# PID.net
KiCad netlist of a schematic drawn in Altium Designer
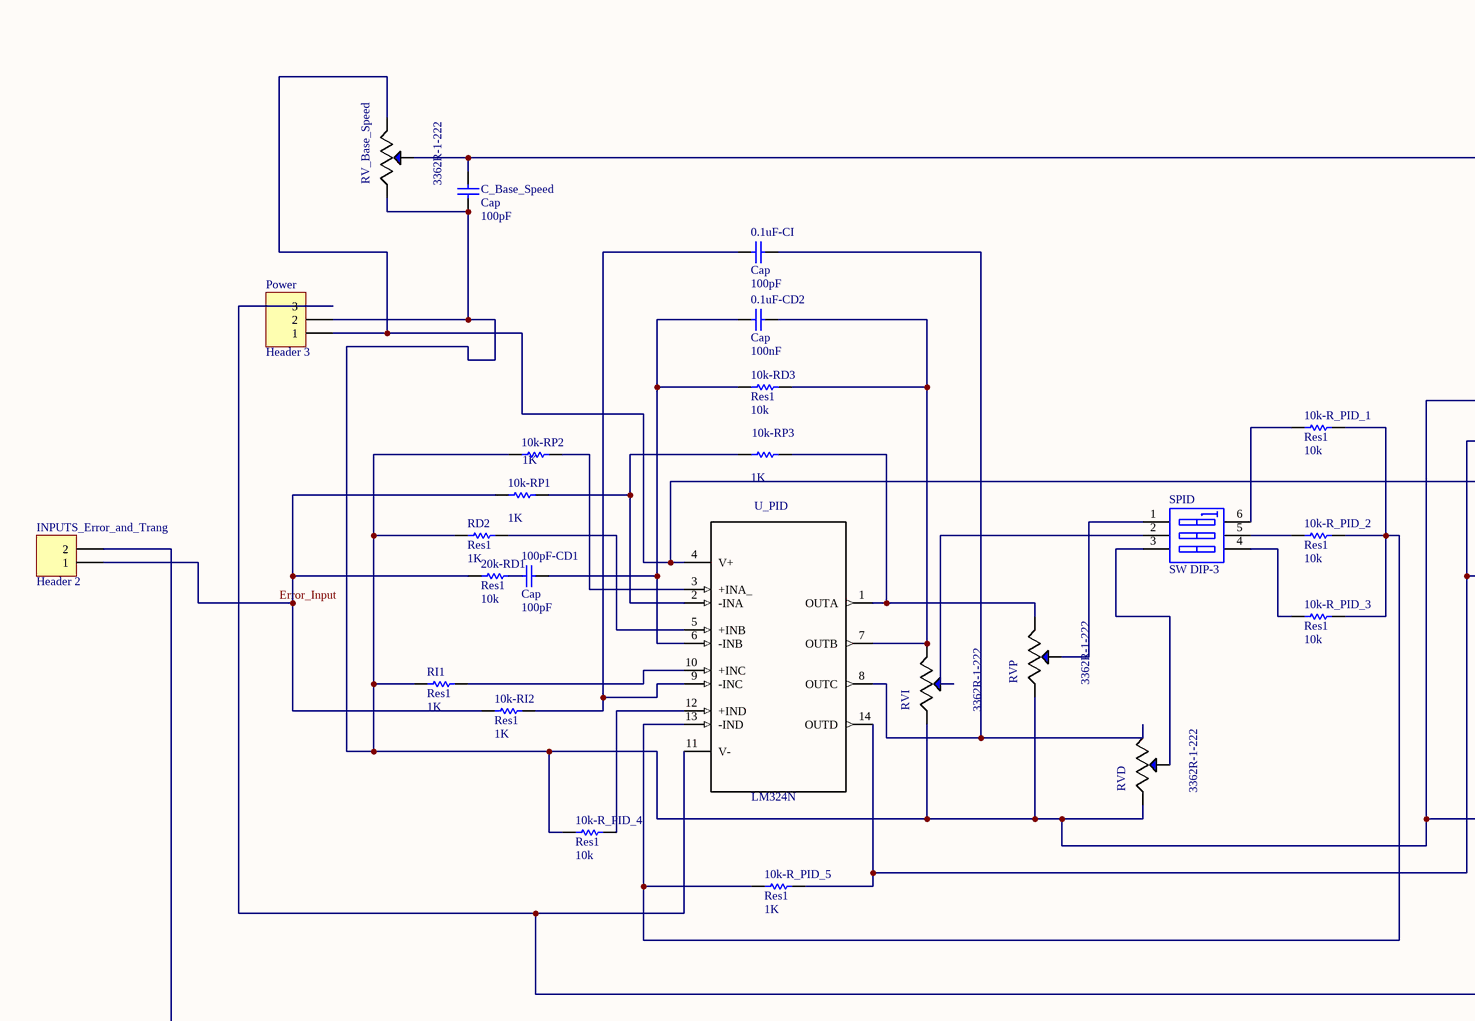
[diagram p0: PID.SchDoc, left]
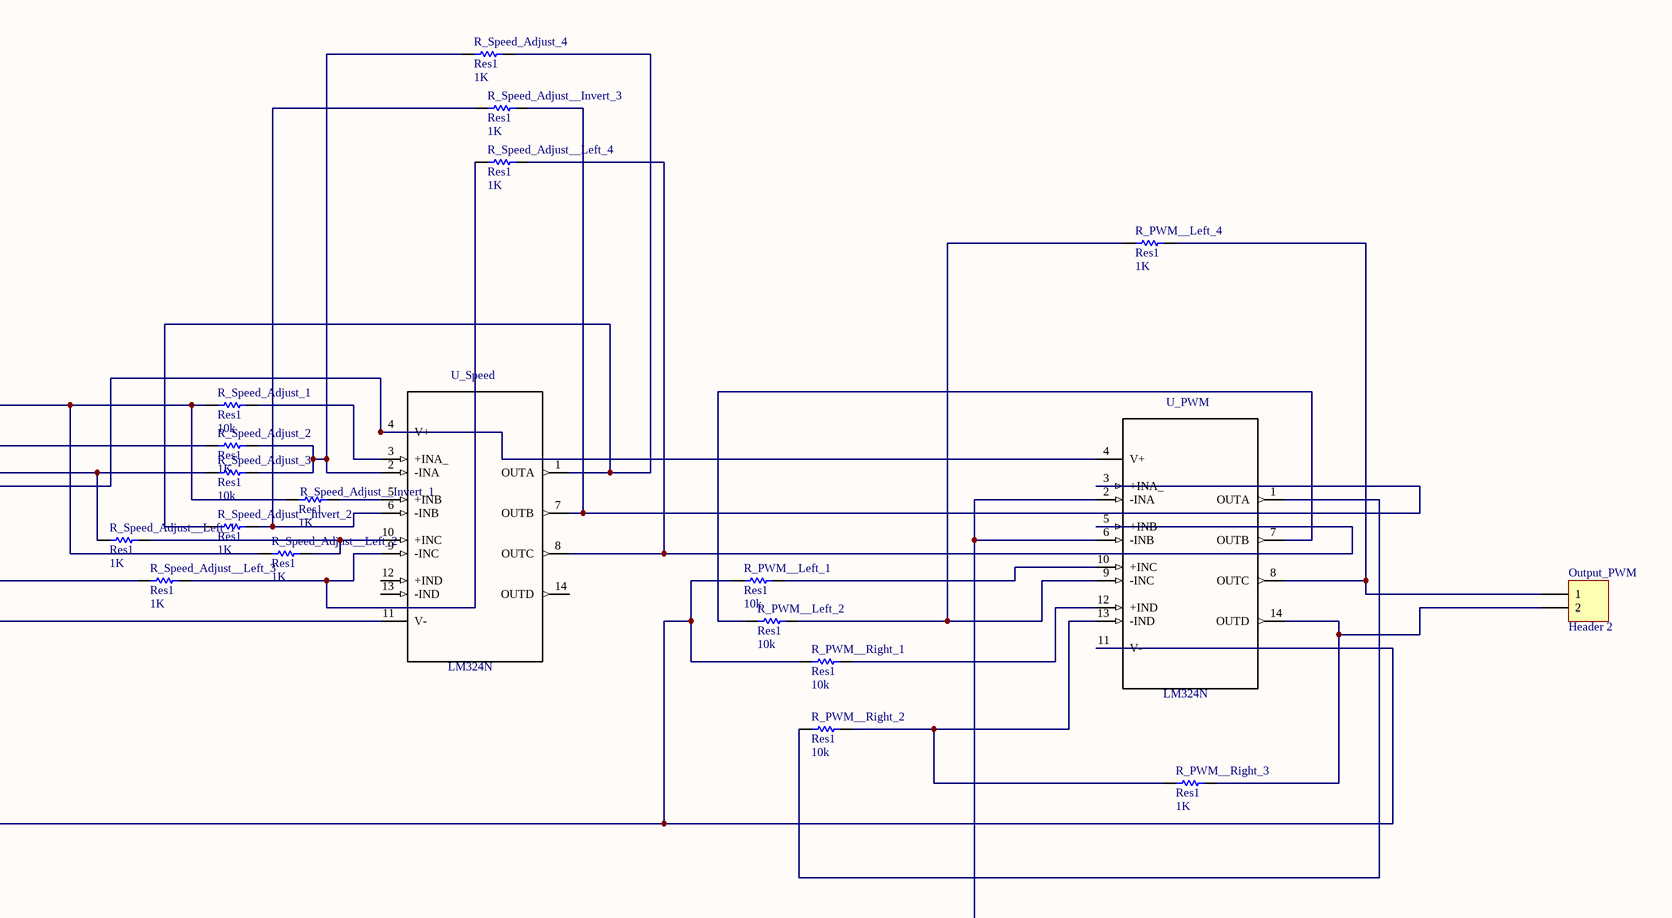
[diagram p1: PID.SchDoc, right]

(export (version "E")
  (design (tool "Eeschema 10.0.6"))
  (components
    (comp (ref "0.1uF-CD2")
      (value "Cap")
      (footprint "RAD-0.3")
      (description "Capacitor")
      (fields (field (name "ALTIUM_VALUE") "100nF") (field (name "PUBLISHER") "Altium Limited"))
      (libsource (lib "Miscellaneous Devices") (part "Cap"))
    )
    (comp (ref "0.1uF-CI")
      (value "Cap")
      (footprint "RAD-0.3")
      (description "Capacitor")
      (fields (field (name "ALTIUM_VALUE") "100pF") (field (name "PUBLISHER") "Altium Limited"))
      (libsource (lib "Miscellaneous Devices") (part "Cap"))
    )
    (comp (ref "10k-RD3")
      (value "Res1")
      (footprint "AXIAL-0.3")
      (description "Resistor")
      (fields (field (name "ALTIUM_VALUE") "10k") (field (name "PUBLISHER") "Altium Limited"))
      (libsource (lib "Miscellaneous Devices") (part "Res1"))
    )
    (comp (ref "10k-RI2")
      (value "Res1")
      (footprint "AXIAL-0.3")
      (description "Resistor")
      (fields (field (name "ALTIUM_VALUE") "1K") (field (name "PUBLISHER") "Altium Limited"))
      (libsource (lib "Miscellaneous Devices") (part "Res1"))
    )
    (comp (ref "10k-RP1")
      (value "1K")
      (footprint "AXIAL-0.3")
      (description "Resistor")
      (fields (field (name "PUBLISHER") "Altium Limited"))
      (libsource (lib "Miscellaneous Devices") (part "Res1"))
    )
    (comp (ref "10k-RP2")
      (value "1K")
      (footprint "AXIAL-0.3")
      (description "Resistor")
      (fields (field (name "PUBLISHER") "Altium Limited"))
      (libsource (lib "Miscellaneous Devices") (part "Res1"))
    )
    (comp (ref "10k-RP3")
      (value "1K")
      (footprint "AXIAL-0.3")
      (description "Resistor")
      (fields (field (name "PUBLISHER") "Altium Limited"))
      (libsource (lib "Miscellaneous Devices") (part "Res1"))
    )
    (comp (ref "10k-R_PID_1")
      (value "Res1")
      (footprint "AXIAL-0.3")
      (description "Resistor")
      (fields (field (name "ALTIUM_VALUE") "10k") (field (name "PUBLISHER") "Altium Limited"))
      (libsource (lib "Miscellaneous Devices") (part "Res1"))
    )
    (comp (ref "10k-R_PID_2")
      (value "Res1")
      (footprint "AXIAL-0.3")
      (description "Resistor")
      (fields (field (name "ALTIUM_VALUE") "10k") (field (name "PUBLISHER") "Altium Limited"))
      (libsource (lib "Miscellaneous Devices") (part "Res1"))
    )
    (comp (ref "10k-R_PID_3")
      (value "Res1")
      (footprint "AXIAL-0.3")
      (description "Resistor")
      (fields (field (name "ALTIUM_VALUE") "10k") (field (name "PUBLISHER") "Altium Limited"))
      (libsource (lib "Miscellaneous Devices") (part "Res1"))
    )
    (comp (ref "10k-R_PID_4")
      (value "Res1")
      (footprint "AXIAL-0.3")
      (description "Resistor")
      (fields (field (name "ALTIUM_VALUE") "10k") (field (name "PUBLISHER") "Altium Limited"))
      (libsource (lib "Miscellaneous Devices") (part "Res1"))
    )
    (comp (ref "10k-R_PID_5")
      (value "Res1")
      (footprint "AXIAL-0.3")
      (description "Resistor")
      (fields (field (name "ALTIUM_VALUE") "1K") (field (name "PUBLISHER") "Altium Limited"))
      (libsource (lib "Miscellaneous Devices") (part "Res1"))
    )
    (comp (ref "20k-RD1")
      (value "Res1")
      (footprint "AXIAL-0.3")
      (description "Resistor")
      (fields (field (name "ALTIUM_VALUE") "10k") (field (name "PUBLISHER") "Altium Limited"))
      (libsource (lib "Miscellaneous Devices") (part "Res1"))
    )
    (comp (ref "100pF-CD1")
      (value "Cap")
      (footprint "RAD-0.3")
      (description "Capacitor")
      (fields (field (name "ALTIUM_VALUE") "100pF") (field (name "PUBLISHER") "Altium Limited"))
      (libsource (lib "Miscellaneous Devices") (part "Cap"))
    )
    (comp (ref "C_Base_Speed")
      (value "Cap")
      (footprint "RAD-0.3")
      (description "Capacitor")
      (fields (field (name "ALTIUM_VALUE") "100pF") (field (name "PUBLISHER") "Altium Limited"))
      (libsource (lib "Miscellaneous Devices") (part "Cap"))
    )
    (comp (ref "INPUTS_Error_and_Trang")
      (value "Header 2")
      (footprint "HDR1X2")
      (description "Header, 2-Pin")
      (fields (field (name "PUBLISHER") "Altium Limited"))
      (libsource (lib "") (part "Header 2_1"))
    )
    (comp (ref "Output_PWM")
      (value "Header 2")
      (footprint "HDR1X2")
      (description "Header, 2-Pin")
      (fields (field (name "PUBLISHER") "Altium Limited"))
      (libsource (lib "Miscellaneous Connectors") (part "Header 2"))
    )
    (comp (ref "Power")
      (value "Header 3")
      (footprint "HDR1X3")
      (description "Header, 3-Pin")
      (fields (field (name "PUBLISHER") "Altium Limited"))
      (libsource (lib "Miscellaneous Connectors") (part "Header 3"))
    )
    (comp (ref "RD2")
      (value "Res1")
      (footprint "AXIAL-0.3")
      (description "Resistor")
      (fields (field (name "ALTIUM_VALUE") "1K") (field (name "PUBLISHER") "Altium Limited"))
      (libsource (lib "Miscellaneous Devices") (part "Res1"))
    )
    (comp (ref "RI1")
      (value "Res1")
      (footprint "AXIAL-0.3")
      (description "Resistor")
      (fields (field (name "ALTIUM_VALUE") "1K") (field (name "PUBLISHER") "Altium Limited"))
      (libsource (lib "Miscellaneous Devices") (part "Res1"))
    )
    (comp (ref "RVD")
      (value "3362R-1-222")
      (footprint "*TRIM_3362R-1-222")
      (description "Trimpot 2.2k Ohm 1/4 Sq Cer St")
      (fields (field (name "MF") "Bourns"))
      (libsource (lib "3362R-1-222") (part "3362R-1-222"))
    )
    (comp (ref "RVI")
      (value "3362R-1-222")
      (footprint "*TRIM_3362R-1-222")
      (description "Trimpot 2.2k Ohm 1/4 Sq Cer St")
      (fields (field (name "MF") "Bourns"))
      (libsource (lib "3362R-1-222") (part "3362R-1-222"))
    )
    (comp (ref "RVP")
      (value "3362R-1-222")
      (footprint "*TRIM_3362R-1-222")
      (description "Trimpot 2.2k Ohm 1/4 Sq Cer St")
      (fields (field (name "MF") "Bourns"))
      (libsource (lib "3362R-1-222") (part "3362R-1-222"))
    )
    (comp (ref "RV_Base_Speed")
      (value "3362R-1-222")
      (footprint "*TRIM_3362R-1-222")
      (description "Trimpot 2.2k Ohm 1/4 Sq Cer St")
      (fields (field (name "MF") "Bourns"))
      (libsource (lib "3362R-1-222") (part "3362R-1-222"))
    )
    (comp (ref "R_PWM__Left_1")
      (value "Res1")
      (footprint "AXIAL-0.3")
      (description "Resistor")
      (fields (field (name "ALTIUM_VALUE") "10k") (field (name "PUBLISHER") "Altium Limited"))
      (libsource (lib "Miscellaneous Devices") (part "Res1"))
    )
    (comp (ref "R_PWM__Left_2")
      (value "Res1")
      (footprint "AXIAL-0.3")
      (description "Resistor")
      (fields (field (name "ALTIUM_VALUE") "10k") (field (name "PUBLISHER") "Altium Limited"))
      (libsource (lib "Miscellaneous Devices") (part "Res1"))
    )
    (comp (ref "R_PWM__Left_4")
      (value "Res1")
      (footprint "AXIAL-0.3")
      (description "Resistor")
      (fields (field (name "ALTIUM_VALUE") "1K") (field (name "PUBLISHER") "Altium Limited"))
      (libsource (lib "Miscellaneous Devices") (part "Res1"))
    )
    (comp (ref "R_PWM__Right_1")
      (value "Res1")
      (footprint "AXIAL-0.3")
      (description "Resistor")
      (fields (field (name "ALTIUM_VALUE") "10k") (field (name "PUBLISHER") "Altium Limited"))
      (libsource (lib "Miscellaneous Devices") (part "Res1"))
    )
    (comp (ref "R_PWM__Right_2")
      (value "Res1")
      (footprint "AXIAL-0.3")
      (description "Resistor")
      (fields (field (name "ALTIUM_VALUE") "10k") (field (name "PUBLISHER") "Altium Limited"))
      (libsource (lib "Miscellaneous Devices") (part "Res1"))
    )
    (comp (ref "R_PWM__Right_3")
      (value "Res1")
      (footprint "AXIAL-0.3")
      (description "Resistor")
      (fields (field (name "ALTIUM_VALUE") "1K") (field (name "PUBLISHER") "Altium Limited"))
      (libsource (lib "Miscellaneous Devices") (part "Res1"))
    )
    (comp (ref "R_Speed_Adjust_1")
      (value "Res1")
      (footprint "AXIAL-0.3")
      (description "Resistor")
      (fields (field (name "ALTIUM_VALUE") "10k") (field (name "PUBLISHER") "Altium Limited"))
      (libsource (lib "Miscellaneous Devices") (part "Res1"))
    )
    (comp (ref "R_Speed_Adjust_2")
      (value "Res1")
      (footprint "AXIAL-0.3")
      (description "Resistor")
      (fields (field (name "ALTIUM_VALUE") "1K") (field (name "PUBLISHER") "Altium Limited"))
      (libsource (lib "Miscellaneous Devices") (part "Res1"))
    )
    (comp (ref "R_Speed_Adjust_3")
      (value "Res1")
      (footprint "AXIAL-0.3")
      (description "Resistor")
      (fields (field (name "ALTIUM_VALUE") "10k") (field (name "PUBLISHER") "Altium Limited"))
      (libsource (lib "Miscellaneous Devices") (part "Res1"))
    )
    (comp (ref "R_Speed_Adjust_4")
      (value "Res1")
      (footprint "AXIAL-0.3")
      (description "Resistor")
      (fields (field (name "ALTIUM_VALUE") "1K") (field (name "PUBLISHER") "Altium Limited"))
      (libsource (lib "Miscellaneous Devices") (part "Res1"))
    )
    (comp (ref "R_Speed_Adjust__Invert_1")
      (value "Res1")
      (footprint "AXIAL-0.3")
      (description "Resistor")
      (fields (field (name "ALTIUM_VALUE") "1K") (field (name "PUBLISHER") "Altium Limited"))
      (libsource (lib "Miscellaneous Devices") (part "Res1"))
    )
    (comp (ref "R_Speed_Adjust__Invert_2")
      (value "Res1")
      (footprint "AXIAL-0.3")
      (description "Resistor")
      (fields (field (name "ALTIUM_VALUE") "1K") (field (name "PUBLISHER") "Altium Limited"))
      (libsource (lib "Miscellaneous Devices") (part "Res1"))
    )
    (comp (ref "R_Speed_Adjust__Invert_3")
      (value "Res1")
      (footprint "AXIAL-0.3")
      (description "Resistor")
      (fields (field (name "ALTIUM_VALUE") "1K") (field (name "PUBLISHER") "Altium Limited"))
      (libsource (lib "Miscellaneous Devices") (part "Res1"))
    )
    (comp (ref "R_Speed_Adjust__Left_1")
      (value "Res1")
      (footprint "AXIAL-0.3")
      (description "Resistor")
      (fields (field (name "ALTIUM_VALUE") "1K") (field (name "PUBLISHER") "Altium Limited"))
      (libsource (lib "Miscellaneous Devices") (part "Res1"))
    )
    (comp (ref "R_Speed_Adjust__Left_2")
      (value "Res1")
      (footprint "AXIAL-0.3")
      (description "Resistor")
      (fields (field (name "ALTIUM_VALUE") "1K") (field (name "PUBLISHER") "Altium Limited"))
      (libsource (lib "Miscellaneous Devices") (part "Res1"))
    )
    (comp (ref "R_Speed_Adjust__Left_3")
      (value "Res1")
      (footprint "AXIAL-0.3")
      (description "Resistor")
      (fields (field (name "ALTIUM_VALUE") "1K") (field (name "PUBLISHER") "Altium Limited"))
      (libsource (lib "Miscellaneous Devices") (part "Res1"))
    )
    (comp (ref "R_Speed_Adjust__Left_4")
      (value "Res1")
      (footprint "AXIAL-0.3")
      (description "Resistor")
      (fields (field (name "ALTIUM_VALUE") "1K") (field (name "PUBLISHER") "Altium Limited"))
      (libsource (lib "Miscellaneous Devices") (part "Res1"))
    )
    (comp (ref "SPID")
      (value "SW DIP-3")
      (footprint "DIP-6")
      (description "DIP Switch, 3 Position, SPST")
      (fields (field (name "PUBLISHER") "Altium Limited"))
      (libsource (lib "Miscellaneous Devices") (part "SW DIP-3"))
    )
    (comp (ref "U_PID")
      (value "LM324N")
      (footprint "*DIP254P762X508-14")
      (description "OP Amp Quad GP ?15V/30V 14-Pin PDIP Tube")
      (fields (field (name "MF") "ON Semiconductor"))
      (libsource (lib "LM324N") (part "LM324N"))
    )
    (comp (ref "U_PWM")
      (value "LM324N")
      (footprint "*DIP254P762X508-14")
      (description "OP Amp Quad GP ?15V/30V 14-Pin PDIP Tube")
      (fields (field (name "MF") "ON Semiconductor"))
      (libsource (lib "LM324N") (part "LM324N"))
    )
    (comp (ref "U_Speed")
      (value "LM324N")
      (footprint "*DIP254P762X508-14")
      (description "OP Amp Quad GP ?15V/30V 14-Pin PDIP Tube")
      (fields (field (name "MF") "ON Semiconductor"))
      (libsource (lib "LM324N") (part "LM324N"))
    )
  )
  (nets
    (net (code "1") (name "/Error_Input") (class "Default")
      (node (ref "10k-RI2") (pin "1") (pinfunction "1_1") (pintype "passive"))
      (node (ref "10k-RP1") (pin "1") (pinfunction "1_1") (pintype "passive"))
      (node (ref "20k-RD1") (pin "1") (pinfunction "1_1") (pintype "passive"))
      (node (ref "INPUTS_Error_and_Trang") (pin "1") (pinfunction "1_1") (pintype "passive"))
    )
    (net (code "2") (name "Net-(100pF-CD1-Pad1)") (class "Default")
      (node (ref "100pF-CD1") (pin "1") (pinfunction "1_1") (pintype "passive"))
      (node (ref "20k-RD1") (pin "2") (pinfunction "2_2") (pintype "passive"))
    )
    (net (code "3") (name "Net-(RVD-CCW)") (class "Default")
      (node (ref "10k-RP2") (pin "1") (pinfunction "1_1") (pintype "passive"))
      (node (ref "10k-R_PID_4") (pin "1") (pinfunction "1_1") (pintype "passive"))
      (node (ref "C_Base_Speed") (pin "1") (pinfunction "1_1") (pintype "passive"))
      (node (ref "Power") (pin "2") (pinfunction "2_2") (pintype "passive"))
      (node (ref "RD2") (pin "1") (pinfunction "1_1") (pintype "passive"))
      (node (ref "RI1") (pin "1") (pinfunction "1_1") (pintype "passive"))
      (node (ref "RVD") (pin "1") (pinfunction "CCW_1") (pintype "passive"))
      (node (ref "RVI") (pin "1") (pinfunction "CCW_1") (pintype "passive"))
      (node (ref "RVP") (pin "1") (pinfunction "CCW_1") (pintype "passive"))
      (node (ref "RV_Base_Speed") (pin "1") (pinfunction "CCW_1") (pintype "passive"))
      (node (ref "R_PWM__Left_1") (pin "1") (pinfunction "1_1") (pintype "passive"))
      (node (ref "R_PWM__Right_1") (pin "1") (pinfunction "1_1") (pintype "passive"))
      (node (ref "R_Speed_Adjust_1") (pin "1") (pinfunction "1_1") (pintype "passive"))
      (node (ref "R_Speed_Adjust__Invert_1") (pin "1") (pinfunction "1_1") (pintype "passive"))
      (node (ref "R_Speed_Adjust__Left_2") (pin "1") (pinfunction "1_1") (pintype "passive"))
      (node (ref "U_PWM") (pin "11") (pinfunction "V-_11") (pintype "passive"))
    )
    (net (code "4") (name "Net-(RVD-CW)") (class "Default")
      (node (ref "0.1uF-CI") (pin "2") (pinfunction "2_2") (pintype "passive"))
      (node (ref "RVD") (pin "3") (pinfunction "CW_3") (pintype "passive"))
      (node (ref "U_PID") (pin "8") (pinfunction "OUTC_8") (pintype "output"))
    )
    (net (code "5") (name "Net-(RVD-WIPER)") (class "Default")
      (node (ref "RVD") (pin "2") (pinfunction "WIPER_2") (pintype "passive"))
      (node (ref "SPID") (pin "3") (pinfunction "A3_3") (pintype "passive"))
    )
    (net (code "6") (name "Net-(RVI-CW)") (class "Default")
      (node (ref "0.1uF-CD2") (pin "2") (pinfunction "2_2") (pintype "passive"))
      (node (ref "10k-RD3") (pin "2") (pinfunction "2_2") (pintype "passive"))
      (node (ref "RVI") (pin "3") (pinfunction "CW_3") (pintype "passive"))
      (node (ref "U_PID") (pin "7") (pinfunction "OUTB_7") (pintype "output"))
    )
    (net (code "7") (name "Net-(RVI-WIPER)") (class "Default")
      (node (ref "RVI") (pin "2") (pinfunction "WIPER_2") (pintype "passive"))
      (node (ref "SPID") (pin "2") (pinfunction "A2_2") (pintype "passive"))
    )
    (net (code "8") (name "Net-(RVP-CW)") (class "Default")
      (node (ref "10k-RP3") (pin "2") (pinfunction "2_2") (pintype "passive"))
      (node (ref "RVP") (pin "3") (pinfunction "CW_3") (pintype "passive"))
      (node (ref "U_PID") (pin "1") (pinfunction "OUTA_1") (pintype "output"))
    )
    (net (code "9") (name "Net-(RVP-WIPER)") (class "Default")
      (node (ref "RVP") (pin "2") (pinfunction "WIPER_2") (pintype "passive"))
      (node (ref "SPID") (pin "1") (pinfunction "A1_1") (pintype "passive"))
    )
    (net (code "10") (name "Net-(RV_Base_Speed-CW)") (class "Default")
      (node (ref "Power") (pin "1") (pinfunction "1_1") (pintype "passive"))
      (node (ref "RV_Base_Speed") (pin "3") (pinfunction "CW_3") (pintype "passive"))
      (node (ref "U_PID") (pin "4") (pinfunction "V+_4") (pintype "passive"))
      (node (ref "U_PWM") (pin "4") (pinfunction "V+_4") (pintype "passive"))
      (node (ref "U_Speed") (pin "4") (pinfunction "V+_4") (pintype "passive"))
    )
    (net (code "11") (name "Net-(RV_Base_Speed-WIPER)") (class "Default")
      (node (ref "C_Base_Speed") (pin "2") (pinfunction "2_2") (pintype "passive"))
      (node (ref "RV_Base_Speed") (pin "2") (pinfunction "WIPER_2") (pintype "passive"))
      (node (ref "R_Speed_Adjust_3") (pin "1") (pinfunction "1_1") (pintype "passive"))
      (node (ref "R_Speed_Adjust__Left_1") (pin "1") (pinfunction "1_1") (pintype "passive"))
    )
    (net (code "12") (name "Net-(SPID-B1)") (class "Default")
      (node (ref "10k-R_PID_1") (pin "1") (pinfunction "1_1") (pintype "passive"))
      (node (ref "SPID") (pin "6") (pinfunction "B1_6") (pintype "passive"))
    )
    (net (code "13") (name "Net-(SPID-B2)") (class "Default")
      (node (ref "10k-R_PID_2") (pin "1") (pinfunction "1_1") (pintype "passive"))
      (node (ref "SPID") (pin "5") (pinfunction "B2_5") (pintype "passive"))
    )
    (net (code "14") (name "Net-(SPID-B3)") (class "Default")
      (node (ref "10k-R_PID_3") (pin "1") (pinfunction "1_1") (pintype "passive"))
      (node (ref "SPID") (pin "4") (pinfunction "B3_4") (pintype "passive"))
    )
    (net (code "15") (name "Net-(U_PID-+INA_)") (class "Default")
      (node (ref "10k-RP2") (pin "2") (pinfunction "2_2") (pintype "passive"))
      (node (ref "U_PID") (pin "3") (pinfunction "+INA__3") (pintype "input"))
    )
    (net (code "16") (name "Net-(U_PID-+INB)") (class "Default")
      (node (ref "RD2") (pin "2") (pinfunction "2_2") (pintype "passive"))
      (node (ref "U_PID") (pin "5") (pinfunction "+INB_5") (pintype "input"))
    )
    (net (code "17") (name "Net-(U_PID-+INC)") (class "Default")
      (node (ref "RI1") (pin "2") (pinfunction "2_2") (pintype "passive"))
      (node (ref "U_PID") (pin "10") (pinfunction "+INC_10") (pintype "input"))
    )
    (net (code "18") (name "Net-(U_PID-+IND)") (class "Default")
      (node (ref "10k-R_PID_4") (pin "2") (pinfunction "2_2") (pintype "passive"))
      (node (ref "U_PID") (pin "12") (pinfunction "+IND_12") (pintype "input"))
    )
    (net (code "19") (name "Net-(U_PID--INA)") (class "Default")
      (node (ref "10k-RP1") (pin "2") (pinfunction "2_2") (pintype "passive"))
      (node (ref "10k-RP3") (pin "1") (pinfunction "1_1") (pintype "passive"))
      (node (ref "U_PID") (pin "2") (pinfunction "-INA_2") (pintype "input"))
    )
    (net (code "20") (name "Net-(U_PID--INB)") (class "Default")
      (node (ref "0.1uF-CD2") (pin "1") (pinfunction "1_1") (pintype "passive"))
      (node (ref "100pF-CD1") (pin "2") (pinfunction "2_2") (pintype "passive"))
      (node (ref "10k-RD3") (pin "1") (pinfunction "1_1") (pintype "passive"))
      (node (ref "U_PID") (pin "6") (pinfunction "-INB_6") (pintype "input"))
    )
    (net (code "21") (name "Net-(U_PID--INC)") (class "Default")
      (node (ref "0.1uF-CI") (pin "1") (pinfunction "1_1") (pintype "passive"))
      (node (ref "10k-RI2") (pin "2") (pinfunction "2_2") (pintype "passive"))
      (node (ref "U_PID") (pin "9") (pinfunction "-INC_9") (pintype "input"))
    )
    (net (code "22") (name "Net-(U_PID--IND)") (class "Default")
      (node (ref "10k-R_PID_1") (pin "2") (pinfunction "2_2") (pintype "passive"))
      (node (ref "10k-R_PID_2") (pin "2") (pinfunction "2_2") (pintype "passive"))
      (node (ref "10k-R_PID_3") (pin "2") (pinfunction "2_2") (pintype "passive"))
      (node (ref "10k-R_PID_5") (pin "1") (pinfunction "1_1") (pintype "passive"))
      (node (ref "U_PID") (pin "13") (pinfunction "-IND_13") (pintype "input"))
    )
    (net (code "23") (name "Net-(U_PID-OUTD)") (class "Default")
      (node (ref "10k-R_PID_5") (pin "2") (pinfunction "2_2") (pintype "passive"))
      (node (ref "R_Speed_Adjust_2") (pin "1") (pinfunction "1_1") (pintype "passive"))
      (node (ref "R_Speed_Adjust__Left_3") (pin "1") (pinfunction "1_1") (pintype "passive"))
      (node (ref "U_PID") (pin "14") (pinfunction "OUTD_14") (pintype "output"))
    )
    (net (code "24") (name "Net-(U_PID-V-)") (class "Default")
      (node (ref "Power") (pin "3") (pinfunction "3_3") (pintype "passive"))
      (node (ref "U_PID") (pin "11") (pinfunction "V-_11") (pintype "passive"))
      (node (ref "U_Speed") (pin "11") (pinfunction "V-_11") (pintype "passive"))
    )
    (net (code "25") (name "Net-(U_PWM-+INA_)") (class "Default")
      (node (ref "R_Speed_Adjust__Invert_3") (pin "2") (pinfunction "2_2") (pintype "passive"))
      (node (ref "U_PWM") (pin "3") (pinfunction "+INA__3") (pintype "input"))
      (node (ref "U_Speed") (pin "7") (pinfunction "OUTB_7") (pintype "output"))
    )
    (net (code "26") (name "Net-(U_PWM-+INB)") (class "Default")
      (node (ref "R_Speed_Adjust__Left_4") (pin "2") (pinfunction "2_2") (pintype "passive"))
      (node (ref "U_PWM") (pin "5") (pinfunction "+INB_5") (pintype "input"))
      (node (ref "U_Speed") (pin "8") (pinfunction "OUTC_8") (pintype "output"))
    )
    (net (code "27") (name "Net-(U_PWM-+INC)") (class "Default")
      (node (ref "R_PWM__Left_1") (pin "2") (pinfunction "2_2") (pintype "passive"))
      (node (ref "U_PWM") (pin "10") (pinfunction "+INC_10") (pintype "input"))
    )
    (net (code "28") (name "Net-(U_PWM-+IND)") (class "Default")
      (node (ref "R_PWM__Right_1") (pin "2") (pinfunction "2_2") (pintype "passive"))
      (node (ref "U_PWM") (pin "12") (pinfunction "+IND_12") (pintype "input"))
    )
    (net (code "29") (name "Net-(U_PWM--INA)") (class "Default")
      (node (ref "INPUTS_Error_and_Trang") (pin "2") (pinfunction "2_2") (pintype "passive"))
      (node (ref "U_PWM") (pin "2") (pinfunction "-INA_2") (pintype "input"))
      (node (ref "U_PWM") (pin "6") (pinfunction "-INB_6") (pintype "input"))
    )
    (net (code "30") (name "Net-(U_PWM--INC)") (class "Default")
      (node (ref "R_PWM__Left_2") (pin "2") (pinfunction "2_2") (pintype "passive"))
      (node (ref "R_PWM__Left_4") (pin "1") (pinfunction "1_1") (pintype "passive"))
      (node (ref "U_PWM") (pin "9") (pinfunction "-INC_9") (pintype "input"))
    )
    (net (code "31") (name "Net-(U_PWM--IND)") (class "Default")
      (node (ref "R_PWM__Right_2") (pin "2") (pinfunction "2_2") (pintype "passive"))
      (node (ref "R_PWM__Right_3") (pin "1") (pinfunction "1_1") (pintype "passive"))
      (node (ref "U_PWM") (pin "13") (pinfunction "-IND_13") (pintype "input"))
    )
    (net (code "32") (name "Net-(U_PWM-OUTA)") (class "Default")
      (node (ref "R_PWM__Right_2") (pin "1") (pinfunction "1_1") (pintype "passive"))
      (node (ref "U_PWM") (pin "1") (pinfunction "OUTA_1") (pintype "output"))
    )
    (net (code "33") (name "Net-(U_PWM-OUTB)") (class "Default")
      (node (ref "R_PWM__Left_2") (pin "1") (pinfunction "1_1") (pintype "passive"))
      (node (ref "U_PWM") (pin "7") (pinfunction "OUTB_7") (pintype "output"))
    )
    (net (code "34") (name "Net-(U_PWM-OUTC)") (class "Default")
      (node (ref "Output_PWM") (pin "1") (pinfunction "1_1") (pintype "passive"))
      (node (ref "R_PWM__Left_4") (pin "2") (pinfunction "2_2") (pintype "passive"))
      (node (ref "U_PWM") (pin "8") (pinfunction "OUTC_8") (pintype "output"))
    )
    (net (code "35") (name "Net-(U_PWM-OUTD)") (class "Default")
      (node (ref "Output_PWM") (pin "2") (pinfunction "2_2") (pintype "passive"))
      (node (ref "R_PWM__Right_3") (pin "2") (pinfunction "2_2") (pintype "passive"))
      (node (ref "U_PWM") (pin "14") (pinfunction "OUTD_14") (pintype "output"))
    )
    (net (code "36") (name "Net-(U_Speed-+INA_)") (class "Default")
      (node (ref "R_Speed_Adjust_1") (pin "2") (pinfunction "2_2") (pintype "passive"))
      (node (ref "U_Speed") (pin "3") (pinfunction "+INA__3") (pintype "input"))
    )
    (net (code "37") (name "Net-(U_Speed-+INB)") (class "Default")
      (node (ref "R_Speed_Adjust__Invert_1") (pin "2") (pinfunction "2_2") (pintype "passive"))
      (node (ref "U_Speed") (pin "5") (pinfunction "+INB_5") (pintype "input"))
    )
    (net (code "38") (name "Net-(U_Speed-+INC)") (class "Default")
      (node (ref "R_Speed_Adjust__Left_1") (pin "2") (pinfunction "2_2") (pintype "passive"))
      (node (ref "R_Speed_Adjust__Left_2") (pin "2") (pinfunction "2_2") (pintype "passive"))
      (node (ref "U_Speed") (pin "10") (pinfunction "+INC_10") (pintype "input"))
    )
    (net (code "39") (name "Net-(U_Speed--INA)") (class "Default")
      (node (ref "R_Speed_Adjust_2") (pin "2") (pinfunction "2_2") (pintype "passive"))
      (node (ref "R_Speed_Adjust_3") (pin "2") (pinfunction "2_2") (pintype "passive"))
      (node (ref "R_Speed_Adjust_4") (pin "1") (pinfunction "1_1") (pintype "passive"))
      (node (ref "U_Speed") (pin "2") (pinfunction "-INA_2") (pintype "input"))
    )
    (net (code "40") (name "Net-(U_Speed--INB)") (class "Default")
      (node (ref "R_Speed_Adjust__Invert_2") (pin "2") (pinfunction "2_2") (pintype "passive"))
      (node (ref "R_Speed_Adjust__Invert_3") (pin "1") (pinfunction "1_1") (pintype "passive"))
      (node (ref "U_Speed") (pin "6") (pinfunction "-INB_6") (pintype "input"))
    )
    (net (code "41") (name "Net-(U_Speed--INC)") (class "Default")
      (node (ref "R_Speed_Adjust__Left_3") (pin "2") (pinfunction "2_2") (pintype "passive"))
      (node (ref "R_Speed_Adjust__Left_4") (pin "1") (pinfunction "1_1") (pintype "passive"))
      (node (ref "U_Speed") (pin "9") (pinfunction "-INC_9") (pintype "input"))
    )
    (net (code "42") (name "Net-(U_Speed-OUTA)") (class "Default")
      (node (ref "R_Speed_Adjust_4") (pin "2") (pinfunction "2_2") (pintype "passive"))
      (node (ref "R_Speed_Adjust__Invert_2") (pin "1") (pinfunction "1_1") (pintype "passive"))
      (node (ref "U_Speed") (pin "1") (pinfunction "OUTA_1") (pintype "output"))
    )
    (net (code "43") (name "unconnected-(U_Speed-+IND-Pad12)") (class "Default")
      (node (ref "U_Speed") (pin "12") (pinfunction "+IND_12") (pintype "input"))
    )
    (net (code "44") (name "unconnected-(U_Speed--IND-Pad13)") (class "Default")
      (node (ref "U_Speed") (pin "13") (pinfunction "-IND_13") (pintype "input"))
    )
    (net (code "45") (name "unconnected-(U_Speed-OUTD-Pad14)") (class "Default")
      (node (ref "U_Speed") (pin "14") (pinfunction "OUTD_14") (pintype "output"))
    )
  )
)
